# draft3_4lyr.net
KiCad netlist of a schematic drawn in EAGLE
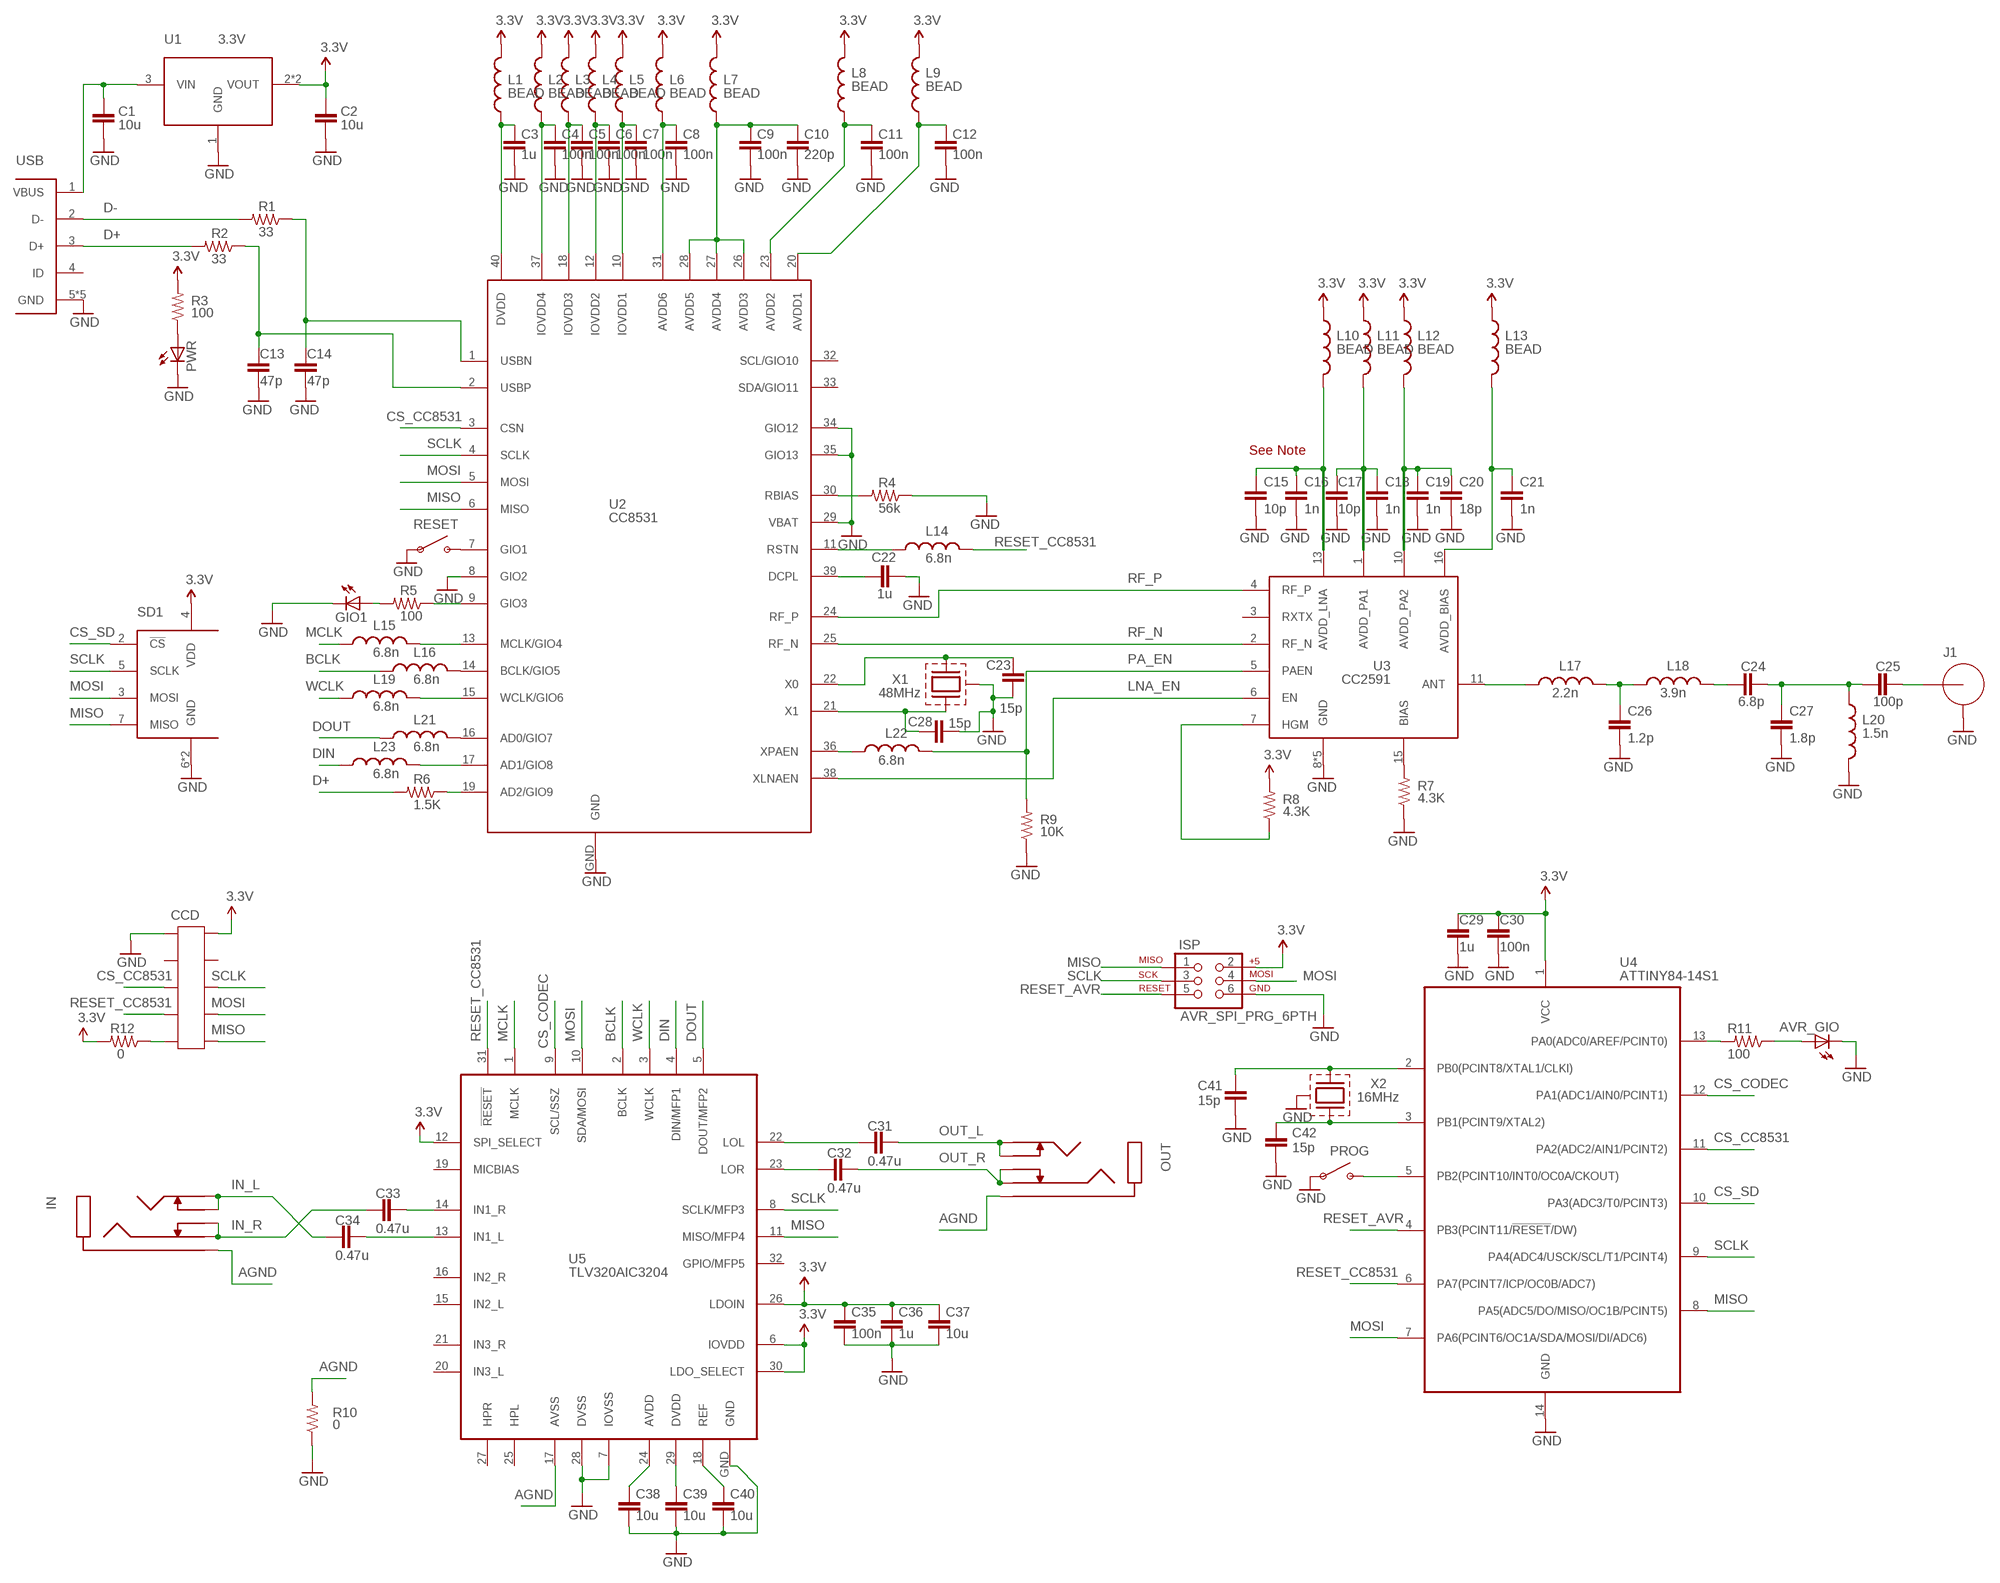
[diagram p0: schematic, sheet 1]

(export (version "E")
  (design (tool "Eeschema 10.0.6"))
  (components
    (comp (ref "AVR_GIO")
      (value "LEDCHIP-LED0603")
      (footprint "eagle-import:CHIP-LED0603")
      (libsource (lib "eagle-import") (part "LEDCHIP-LED0603"))
    )
    (comp (ref "C1")
      (value "10u")
      (footprint "eagle-import:C0603")
      (libsource (lib "eagle-import") (part "C-EUC0603"))
    )
    (comp (ref "C2")
      (value "10u")
      (footprint "eagle-import:C0603")
      (libsource (lib "eagle-import") (part "C-EUC0603"))
    )
    (comp (ref "C3")
      (value "1u")
      (footprint "eagle-import:C0603")
      (libsource (lib "eagle-import") (part "C-EUC0603"))
    )
    (comp (ref "C4")
      (value "100n")
      (footprint "eagle-import:C0603")
      (libsource (lib "eagle-import") (part "C-EUC0603"))
    )
    (comp (ref "C5")
      (value "100n")
      (footprint "eagle-import:C0603")
      (libsource (lib "eagle-import") (part "C-EUC0603"))
    )
    (comp (ref "C6")
      (value "100n")
      (footprint "eagle-import:C0603")
      (libsource (lib "eagle-import") (part "C-EUC0603"))
    )
    (comp (ref "C7")
      (value "100n")
      (footprint "eagle-import:C0603")
      (libsource (lib "eagle-import") (part "C-EUC0603"))
    )
    (comp (ref "C8")
      (value "100n")
      (footprint "eagle-import:C0603")
      (libsource (lib "eagle-import") (part "C-EUC0603"))
    )
    (comp (ref "C9")
      (value "100n")
      (footprint "eagle-import:C0603")
      (libsource (lib "eagle-import") (part "C-EUC0603"))
    )
    (comp (ref "C10")
      (value "220p")
      (footprint "eagle-import:C0603")
      (libsource (lib "eagle-import") (part "C-EUC0603"))
    )
    (comp (ref "C11")
      (value "100n")
      (footprint "eagle-import:C0603")
      (libsource (lib "eagle-import") (part "C-EUC0603"))
    )
    (comp (ref "C12")
      (value "100n")
      (footprint "eagle-import:C0603")
      (libsource (lib "eagle-import") (part "C-EUC0603"))
    )
    (comp (ref "C13")
      (value "47p")
      (footprint "eagle-import:C0603")
      (libsource (lib "eagle-import") (part "C-EUC0603"))
    )
    (comp (ref "C14")
      (value "47p")
      (footprint "eagle-import:C0603")
      (libsource (lib "eagle-import") (part "C-EUC0603"))
    )
    (comp (ref "C15")
      (value "10p")
      (footprint "eagle-import:C0603")
      (libsource (lib "eagle-import") (part "C-EUC0603"))
    )
    (comp (ref "C16")
      (value "1n")
      (footprint "eagle-import:C0603")
      (libsource (lib "eagle-import") (part "C-EUC0603"))
    )
    (comp (ref "C17")
      (value "10p")
      (footprint "eagle-import:C0603")
      (libsource (lib "eagle-import") (part "C-EUC0603"))
    )
    (comp (ref "C18")
      (value "1n")
      (footprint "eagle-import:C0603")
      (libsource (lib "eagle-import") (part "C-EUC0603"))
    )
    (comp (ref "C19")
      (value "1n")
      (footprint "eagle-import:C0603")
      (libsource (lib "eagle-import") (part "C-EUC0603"))
    )
    (comp (ref "C20")
      (value "18p")
      (footprint "eagle-import:C0603")
      (libsource (lib "eagle-import") (part "C-EUC0603"))
    )
    (comp (ref "C21")
      (value "1n")
      (footprint "eagle-import:C0603")
      (libsource (lib "eagle-import") (part "C-EUC0603"))
    )
    (comp (ref "C22")
      (value "1u")
      (footprint "eagle-import:C0603")
      (libsource (lib "eagle-import") (part "C-EUC0603"))
    )
    (comp (ref "C23")
      (value "15p")
      (footprint "eagle-import:C0603")
      (libsource (lib "eagle-import") (part "C-EUC0603"))
    )
    (comp (ref "C24")
      (value "6.8p")
      (footprint "eagle-import:C0603")
      (libsource (lib "eagle-import") (part "C-EUC0603"))
    )
    (comp (ref "C25")
      (value "100p")
      (footprint "eagle-import:C0603")
      (libsource (lib "eagle-import") (part "C-EUC0603"))
    )
    (comp (ref "C26")
      (value "1.2p")
      (footprint "eagle-import:C0603")
      (libsource (lib "eagle-import") (part "C-EUC0603"))
    )
    (comp (ref "C27")
      (value "1.8p")
      (footprint "eagle-import:C0603")
      (libsource (lib "eagle-import") (part "C-EUC0603"))
    )
    (comp (ref "C28")
      (value "15p")
      (footprint "eagle-import:C0603")
      (libsource (lib "eagle-import") (part "C-EUC0603"))
    )
    (comp (ref "C29")
      (value "1u")
      (footprint "eagle-import:C0603")
      (libsource (lib "eagle-import") (part "C-EUC0603"))
    )
    (comp (ref "C30")
      (value "100n")
      (footprint "eagle-import:C0603")
      (libsource (lib "eagle-import") (part "C-EUC0603"))
    )
    (comp (ref "C31")
      (value "0.47u")
      (footprint "eagle-import:C0603")
      (libsource (lib "eagle-import") (part "C-EUC0603"))
    )
    (comp (ref "C32")
      (value "0.47u")
      (footprint "eagle-import:C0603")
      (libsource (lib "eagle-import") (part "C-EUC0603"))
    )
    (comp (ref "C33")
      (value "0.47u")
      (footprint "eagle-import:C0603")
      (libsource (lib "eagle-import") (part "C-EUC0603"))
    )
    (comp (ref "C34")
      (value "0.47u")
      (footprint "eagle-import:C0603")
      (libsource (lib "eagle-import") (part "C-EUC0603"))
    )
    (comp (ref "C35")
      (value "100n")
      (footprint "eagle-import:C0603")
      (libsource (lib "eagle-import") (part "C-EUC0603"))
    )
    (comp (ref "C36")
      (value "1u")
      (footprint "eagle-import:C0603")
      (libsource (lib "eagle-import") (part "C-EUC0603"))
    )
    (comp (ref "C37")
      (value "10u")
      (footprint "eagle-import:C0603")
      (libsource (lib "eagle-import") (part "C-EUC0603"))
    )
    (comp (ref "C38")
      (value "10u")
      (footprint "eagle-import:C0603")
      (libsource (lib "eagle-import") (part "C-EUC0603"))
    )
    (comp (ref "C39")
      (value "10u")
      (footprint "eagle-import:C0603")
      (libsource (lib "eagle-import") (part "C-EUC0603"))
    )
    (comp (ref "C40")
      (value "10u")
      (footprint "eagle-import:C0603")
      (libsource (lib "eagle-import") (part "C-EUC0603"))
    )
    (comp (ref "C41")
      (value "15p")
      (footprint "eagle-import:C0603")
      (libsource (lib "eagle-import") (part "C-EUC0603"))
    )
    (comp (ref "C42")
      (value "15p")
      (footprint "eagle-import:C0603")
      (libsource (lib "eagle-import") (part "C-EUC0603"))
    )
    (comp (ref "CCD")
      (value "HEADER-10P-PTH-MALE")
      (footprint "eagle-import:2X5")
      (libsource (lib "eagle-import") (part "HEADER-10P-PTH-MALE"))
    )
    (comp (ref "GIO1")
      (value "LEDCHIP-LED0603")
      (footprint "eagle-import:CHIP-LED0603")
      (libsource (lib "eagle-import") (part "LEDCHIP-LED0603"))
    )
    (comp (ref "IN")
      (value "PHONE_SW")
      (footprint "eagle-import:35RAPC4BV4")
      (libsource (lib "eagle-import") (part "PHONE_SW"))
    )
    (comp (ref "ISP")
      (value "AVR_SPI_PRG_6PTH")
      (footprint "eagle-import:2X3")
      (libsource (lib "eagle-import") (part "AVR_SPI_PRG_6PTH"))
    )
    (comp (ref "J1")
      (value "SMA")
      (footprint "eagle-import:CONSMA003.031")
      (libsource (lib "eagle-import") (part "SMA"))
    )
    (comp (ref "L1")
      (value "BEAD")
      (footprint "eagle-import:0603")
      (libsource (lib "eagle-import") (part "INDUCTOR0603"))
    )
    (comp (ref "L2")
      (value "BEAD")
      (footprint "eagle-import:0603")
      (libsource (lib "eagle-import") (part "INDUCTOR0603"))
    )
    (comp (ref "L3")
      (value "BEAD")
      (footprint "eagle-import:0603")
      (libsource (lib "eagle-import") (part "INDUCTOR0603"))
    )
    (comp (ref "L4")
      (value "BEAD")
      (footprint "eagle-import:0603")
      (libsource (lib "eagle-import") (part "INDUCTOR0603"))
    )
    (comp (ref "L5")
      (value "BEAD")
      (footprint "eagle-import:0603")
      (libsource (lib "eagle-import") (part "INDUCTOR0603"))
    )
    (comp (ref "L6")
      (value "BEAD")
      (footprint "eagle-import:0603")
      (libsource (lib "eagle-import") (part "INDUCTOR0603"))
    )
    (comp (ref "L7")
      (value "BEAD")
      (footprint "eagle-import:0603")
      (libsource (lib "eagle-import") (part "INDUCTOR0603"))
    )
    (comp (ref "L8")
      (value "BEAD")
      (footprint "eagle-import:0603")
      (libsource (lib "eagle-import") (part "INDUCTOR0603"))
    )
    (comp (ref "L9")
      (value "BEAD")
      (footprint "eagle-import:0603")
      (libsource (lib "eagle-import") (part "INDUCTOR0603"))
    )
    (comp (ref "L10")
      (value "BEAD")
      (footprint "eagle-import:0603")
      (libsource (lib "eagle-import") (part "INDUCTOR0603"))
    )
    (comp (ref "L11")
      (value "BEAD")
      (footprint "eagle-import:0603")
      (libsource (lib "eagle-import") (part "INDUCTOR0603"))
    )
    (comp (ref "L12")
      (value "BEAD")
      (footprint "eagle-import:0603")
      (libsource (lib "eagle-import") (part "INDUCTOR0603"))
    )
    (comp (ref "L13")
      (value "BEAD")
      (footprint "eagle-import:0603")
      (libsource (lib "eagle-import") (part "INDUCTOR0603"))
    )
    (comp (ref "L14")
      (value "6.8n")
      (footprint "eagle-import:0603")
      (libsource (lib "eagle-import") (part "INDUCTOR0603"))
    )
    (comp (ref "L15")
      (value "6.8n")
      (footprint "eagle-import:0603")
      (libsource (lib "eagle-import") (part "INDUCTOR0603"))
    )
    (comp (ref "L16")
      (value "6.8n")
      (footprint "eagle-import:0603")
      (libsource (lib "eagle-import") (part "INDUCTOR0603"))
    )
    (comp (ref "L17")
      (value "2.2n")
      (footprint "eagle-import:0603")
      (libsource (lib "eagle-import") (part "INDUCTOR0603"))
    )
    (comp (ref "L18")
      (value "3.9n")
      (footprint "eagle-import:0603")
      (libsource (lib "eagle-import") (part "INDUCTOR0603"))
    )
    (comp (ref "L19")
      (value "6.8n")
      (footprint "eagle-import:0603")
      (libsource (lib "eagle-import") (part "INDUCTOR0603"))
    )
    (comp (ref "L20")
      (value "1.5n")
      (footprint "eagle-import:0603")
      (libsource (lib "eagle-import") (part "INDUCTOR0603"))
    )
    (comp (ref "L21")
      (value "6.8n")
      (footprint "eagle-import:0603")
      (libsource (lib "eagle-import") (part "INDUCTOR0603"))
    )
    (comp (ref "L22")
      (value "6.8n")
      (footprint "eagle-import:0603")
      (libsource (lib "eagle-import") (part "INDUCTOR0603"))
    )
    (comp (ref "L23")
      (value "6.8n")
      (footprint "eagle-import:0603")
      (libsource (lib "eagle-import") (part "INDUCTOR0603"))
    )
    (comp (ref "OUT")
      (value "PHONE_SW")
      (footprint "eagle-import:35RAPC4BV4")
      (libsource (lib "eagle-import") (part "PHONE_SW"))
    )
    (comp (ref "PROG")
      (value "SPST-SMD")
      (footprint "eagle-import:TACT_SW")
      (libsource (lib "eagle-import") (part "SPST-SMD"))
    )
    (comp (ref "PWR")
      (value "LEDCHIP-LED0603")
      (footprint "eagle-import:CHIP-LED0603")
      (libsource (lib "eagle-import") (part "LEDCHIP-LED0603"))
    )
    (comp (ref "R1")
      (value "33")
      (footprint "eagle-import:R0603")
      (libsource (lib "eagle-import") (part "R-US_R0603"))
    )
    (comp (ref "R2")
      (value "33")
      (footprint "eagle-import:R0603")
      (libsource (lib "eagle-import") (part "R-US_R0603"))
    )
    (comp (ref "R3")
      (value "100")
      (footprint "eagle-import:R0603")
      (libsource (lib "eagle-import") (part "R-US_R0603"))
    )
    (comp (ref "R4")
      (value "56k")
      (footprint "eagle-import:R0603")
      (libsource (lib "eagle-import") (part "R-US_R0603"))
    )
    (comp (ref "R5")
      (value "100")
      (footprint "eagle-import:R0603")
      (libsource (lib "eagle-import") (part "R-US_R0603"))
    )
    (comp (ref "R6")
      (value "1.5K")
      (footprint "eagle-import:R0603")
      (libsource (lib "eagle-import") (part "R-US_R0603"))
    )
    (comp (ref "R7")
      (value "4.3K")
      (footprint "eagle-import:R0603")
      (libsource (lib "eagle-import") (part "R-US_R0603"))
    )
    (comp (ref "R8")
      (value "4.3K")
      (footprint "eagle-import:R0603")
      (libsource (lib "eagle-import") (part "R-US_R0603"))
    )
    (comp (ref "R9")
      (value "10K")
      (footprint "eagle-import:R0603")
      (libsource (lib "eagle-import") (part "R-US_R0603"))
    )
    (comp (ref "R10")
      (value "0")
      (footprint "eagle-import:R0603")
      (libsource (lib "eagle-import") (part "R-US_R0603"))
    )
    (comp (ref "R11")
      (value "100")
      (footprint "eagle-import:R0603")
      (libsource (lib "eagle-import") (part "R-US_R0603"))
    )
    (comp (ref "R12")
      (value "0")
      (footprint "eagle-import:R0603")
      (libsource (lib "eagle-import") (part "R-US_R0603"))
    )
    (comp (ref "RESET")
      (value "SPST-SMD")
      (footprint "eagle-import:TACT_SW")
      (libsource (lib "eagle-import") (part "SPST-SMD"))
    )
    (comp (ref "SD1")
      (value "MICROSDDM3AT")
      (footprint "eagle-import:DM3AT")
      (libsource (lib "eagle-import") (part "MICROSDDM3AT"))
    )
    (comp (ref "U1")
      (value "3.3V")
      (footprint "eagle-import:SOT-223")
      (libsource (lib "eagle-import") (part "NX1117C"))
    )
    (comp (ref "U2")
      (value "CC8531")
      (footprint "eagle-import:S-PVQFN-N40")
      (libsource (lib "eagle-import") (part "CC8531"))
    )
    (comp (ref "U3")
      (value "CC2591")
      (footprint "eagle-import:S-PVQFN-N16")
      (libsource (lib "eagle-import") (part "CC2591"))
    )
    (comp (ref "U4")
      (value "ATTINY84-14S1")
      (footprint "eagle-import:SOIC14")
      (libsource (lib "eagle-import") (part "ATTINY84-14S1"))
    )
    (comp (ref "U5")
      (value "TLV320AIC3204")
      (footprint "eagle-import:S-PVQFN-N32")
      (libsource (lib "eagle-import") (part "TLV320AIC3204"))
    )
    (comp (ref "USB")
      (value "USB_MICRO_AB")
      (footprint "eagle-import:USB_MICRO_AB")
      (libsource (lib "eagle-import") (part "USB_MICRO_AB"))
    )
    (comp (ref "X1")
      (value "48MHz")
      (footprint "eagle-import:ABM3C")
      (libsource (lib "eagle-import") (part "XTAL-ABRACONABM3C"))
    )
    (comp (ref "X2")
      (value "16MHz")
      (footprint "eagle-import:ABMM")
      (libsource (lib "eagle-import") (part "XTAL-ABRACONABMM"))
    )
  )
  (nets
    (net (code "1") (name "/AGND") (class "Default")
      (node (ref "IN") (pin "1") (pinfunction "GND_1") (pintype "bidirectional"))
      (node (ref "OUT") (pin "1") (pinfunction "GND_1") (pintype "bidirectional"))
      (node (ref "R10") (pin "2") (pinfunction "2_2") (pintype "passive"))
      (node (ref "U5") (pin "17") (pinfunction "AVSS_17") (pintype "bidirectional"))
    )
    (net (code "2") (name "/BCLK") (class "Default")
      (node (ref "L16") (pin "1") (pinfunction "1_1") (pintype "passive"))
      (node (ref "U5") (pin "2") (pinfunction "BCLK_2") (pintype "bidirectional"))
    )
    (net (code "3") (name "/CS_CC8531") (class "Default")
      (node (ref "CCD") (pin "5") (pinfunction "5_5") (pintype "bidirectional"))
      (node (ref "U2") (pin "3") (pinfunction "CSN_3") (pintype "bidirectional"))
      (node (ref "U4") (pin "11") (pinfunction "PA2(ADC2/AIN1/PCINT2)_11") (pintype "bidirectional"))
    )
    (net (code "4") (name "/CS_CODEC") (class "Default")
      (node (ref "U4") (pin "12") (pinfunction "PA1(ADC1/AIN0/PCINT1)_12") (pintype "bidirectional"))
      (node (ref "U5") (pin "9") (pinfunction "SCL/SSZ_9") (pintype "bidirectional"))
    )
    (net (code "5") (name "/CS_SD") (class "Default")
      (node (ref "SD1") (pin "2") (pinfunction "~{CS}_2") (pintype "bidirectional"))
      (node (ref "U4") (pin "10") (pinfunction "PA3(ADC3/T0/PCINT3)_10") (pintype "bidirectional"))
    )
    (net (code "6") (name "/D+") (class "Default")
      (node (ref "R2") (pin "2") (pinfunction "2_2") (pintype "passive"))
      (node (ref "R6") (pin "2") (pinfunction "2_2") (pintype "passive"))
      (node (ref "USB") (pin "3") (pinfunction "D+_3") (pintype "bidirectional"))
    )
    (net (code "7") (name "/D-") (class "Default")
      (node (ref "R1") (pin "2") (pinfunction "2_2") (pintype "passive"))
      (node (ref "USB") (pin "2") (pinfunction "D-_2") (pintype "bidirectional"))
    )
    (net (code "8") (name "/DIN") (class "Default")
      (node (ref "L23") (pin "1") (pinfunction "1_1") (pintype "passive"))
      (node (ref "U5") (pin "4") (pinfunction "DIN/MFP1_4") (pintype "bidirectional"))
    )
    (net (code "9") (name "/DOUT") (class "Default")
      (node (ref "L21") (pin "1") (pinfunction "1_1") (pintype "passive"))
      (node (ref "U5") (pin "5") (pinfunction "DOUT/MFP2_5") (pintype "bidirectional"))
    )
    (net (code "10") (name "/IN_L") (class "Default")
      (node (ref "C34") (pin "1") (pinfunction "1_1") (pintype "passive"))
      (node (ref "IN") (pin "2") (pinfunction "L_2") (pintype "bidirectional"))
      (node (ref "IN") (pin "5") (pinfunction "L_SW_5") (pintype "bidirectional"))
    )
    (net (code "11") (name "/IN_R") (class "Default")
      (node (ref "C33") (pin "1") (pinfunction "1_1") (pintype "passive"))
      (node (ref "IN") (pin "3") (pinfunction "R_SW_3") (pintype "bidirectional"))
      (node (ref "IN") (pin "4") (pinfunction "R_4") (pintype "bidirectional"))
    )
    (net (code "12") (name "/LNA_EN") (class "Default")
      (node (ref "U2") (pin "38") (pinfunction "XLNAEN_38") (pintype "bidirectional"))
      (node (ref "U3") (pin "6") (pinfunction "EN_6") (pintype "bidirectional"))
    )
    (net (code "13") (name "/MCLK") (class "Default")
      (node (ref "L15") (pin "1") (pinfunction "1_1") (pintype "passive"))
      (node (ref "U5") (pin "1") (pinfunction "MCLK_1") (pintype "bidirectional"))
    )
    (net (code "14") (name "/MISO") (class "Default")
      (node (ref "CCD") (pin "10") (pinfunction "10_10") (pintype "bidirectional"))
      (node (ref "ISP") (pin "1") (pinfunction "1_1") (pintype "passive"))
      (node (ref "SD1") (pin "7") (pinfunction "MISO_7") (pintype "bidirectional"))
      (node (ref "U2") (pin "6") (pinfunction "MISO_6") (pintype "bidirectional"))
      (node (ref "U4") (pin "8") (pinfunction "PA5(ADC5/DO/MISO/OC1B/PCINT5)_8") (pintype "bidirectional"))
      (node (ref "U5") (pin "11") (pinfunction "MISO/MFP4_11") (pintype "bidirectional"))
    )
    (net (code "15") (name "/MOSI") (class "Default")
      (node (ref "CCD") (pin "8") (pinfunction "8_8") (pintype "bidirectional"))
      (node (ref "ISP") (pin "4") (pinfunction "4_4") (pintype "passive"))
      (node (ref "SD1") (pin "3") (pinfunction "MOSI_3") (pintype "bidirectional"))
      (node (ref "U2") (pin "5") (pinfunction "MOSI_5") (pintype "bidirectional"))
      (node (ref "U4") (pin "7") (pinfunction "PA6(PCINT6/OC1A/SDA/MOSI/DI/ADC6)_7") (pintype "bidirectional"))
      (node (ref "U5") (pin "10") (pinfunction "SDA/MOSI_10") (pintype "bidirectional"))
    )
    (net (code "16") (name "/OUT_L") (class "Default")
      (node (ref "C31") (pin "2") (pinfunction "2_2") (pintype "passive"))
      (node (ref "OUT") (pin "2") (pinfunction "L_2") (pintype "bidirectional"))
      (node (ref "OUT") (pin "5") (pinfunction "L_SW_5") (pintype "bidirectional"))
    )
    (net (code "17") (name "/OUT_R") (class "Default")
      (node (ref "C32") (pin "2") (pinfunction "2_2") (pintype "passive"))
      (node (ref "OUT") (pin "3") (pinfunction "R_SW_3") (pintype "bidirectional"))
      (node (ref "OUT") (pin "4") (pinfunction "R_4") (pintype "bidirectional"))
    )
    (net (code "18") (name "/PA_EN") (class "Default")
      (node (ref "L22") (pin "2") (pinfunction "2_2") (pintype "passive"))
      (node (ref "R9") (pin "2") (pinfunction "2_2") (pintype "passive"))
      (node (ref "U3") (pin "5") (pinfunction "PAEN_5") (pintype "bidirectional"))
    )
    (net (code "19") (name "/RESET_AVR") (class "Default")
      (node (ref "ISP") (pin "5") (pinfunction "5_5") (pintype "passive"))
      (node (ref "U4") (pin "4") (pinfunction "PB3(PCINT11/~{RESET}/DW)_4") (pintype "bidirectional"))
    )
    (net (code "20") (name "/RESET_CC8531") (class "Default")
      (node (ref "CCD") (pin "7") (pinfunction "7_7") (pintype "bidirectional"))
      (node (ref "L14") (pin "2") (pinfunction "2_2") (pintype "passive"))
      (node (ref "U4") (pin "6") (pinfunction "PA7(PCINT7/ICP/OC0B/ADC7)_6") (pintype "bidirectional"))
      (node (ref "U5") (pin "31") (pinfunction "~{RESET}_31") (pintype "bidirectional"))
    )
    (net (code "21") (name "/RF_N") (class "Default")
      (node (ref "U2") (pin "25") (pinfunction "RF_N_25") (pintype "bidirectional"))
      (node (ref "U3") (pin "2") (pinfunction "RF_N_2") (pintype "bidirectional"))
    )
    (net (code "22") (name "/RF_P") (class "Default")
      (node (ref "U2") (pin "24") (pinfunction "RF_P_24") (pintype "bidirectional"))
      (node (ref "U3") (pin "4") (pinfunction "RF_P_4") (pintype "bidirectional"))
    )
    (net (code "23") (name "/SCLK") (class "Default")
      (node (ref "CCD") (pin "6") (pinfunction "6_6") (pintype "bidirectional"))
      (node (ref "ISP") (pin "3") (pinfunction "3_3") (pintype "passive"))
      (node (ref "SD1") (pin "5") (pinfunction "SCLK_5") (pintype "bidirectional"))
      (node (ref "U2") (pin "4") (pinfunction "SCLK_4") (pintype "bidirectional"))
      (node (ref "U4") (pin "9") (pinfunction "PA4(ADC4/USCK/SCL/T1/PCINT4)_9") (pintype "bidirectional"))
      (node (ref "U5") (pin "8") (pinfunction "SCLK/MFP3_8") (pintype "bidirectional"))
    )
    (net (code "24") (name "/WCLK") (class "Default")
      (node (ref "L19") (pin "1") (pinfunction "1_1") (pintype "passive"))
      (node (ref "U5") (pin "3") (pinfunction "WCLK_3") (pintype "bidirectional"))
    )
    (net (code "25") (name "3.3V") (class "Default")
      (node (ref "C2") (pin "1") (pinfunction "1_1") (pintype "passive"))
      (node (ref "C29") (pin "1") (pinfunction "1_1") (pintype "passive"))
      (node (ref "C30") (pin "1") (pinfunction "1_1") (pintype "passive"))
      (node (ref "C35") (pin "1") (pinfunction "1_1") (pintype "passive"))
      (node (ref "C36") (pin "1") (pinfunction "1_1") (pintype "passive"))
      (node (ref "C37") (pin "1") (pinfunction "1_1") (pintype "passive"))
      (node (ref "CCD") (pin "2") (pinfunction "2_2") (pintype "bidirectional"))
      (node (ref "ISP") (pin "2") (pinfunction "2_2") (pintype "passive"))
      (node (ref "L1") (pin "2") (pinfunction "2_2") (pintype "passive"))
      (node (ref "L10") (pin "1") (pinfunction "1_1") (pintype "passive"))
      (node (ref "L11") (pin "1") (pinfunction "1_1") (pintype "passive"))
      (node (ref "L12") (pin "1") (pinfunction "1_1") (pintype "passive"))
      (node (ref "L13") (pin "1") (pinfunction "1_1") (pintype "passive"))
      (node (ref "L2") (pin "2") (pinfunction "2_2") (pintype "passive"))
      (node (ref "L3") (pin "2") (pinfunction "2_2") (pintype "passive"))
      (node (ref "L4") (pin "2") (pinfunction "2_2") (pintype "passive"))
      (node (ref "L5") (pin "2") (pinfunction "2_2") (pintype "passive"))
      (node (ref "L6") (pin "2") (pinfunction "2_2") (pintype "passive"))
      (node (ref "L7") (pin "2") (pinfunction "2_2") (pintype "passive"))
      (node (ref "L8") (pin "2") (pinfunction "2_2") (pintype "passive"))
      (node (ref "L9") (pin "2") (pinfunction "2_2") (pintype "passive"))
      (node (ref "R12") (pin "2") (pinfunction "2_2") (pintype "passive"))
      (node (ref "R3") (pin "2") (pinfunction "2_2") (pintype "passive"))
      (node (ref "R8") (pin "2") (pinfunction "2_2") (pintype "passive"))
      (node (ref "SD1") (pin "4") (pinfunction "VDD_4") (pintype "bidirectional"))
      (node (ref "U1") (pin "2") (pinfunction "VOUT_2") (pintype "bidirectional"))
      (node (ref "U1") (pin "4") (pinfunction "VOUT_4") (pintype "bidirectional"))
      (node (ref "U4") (pin "1") (pinfunction "VCC_1") (pintype "bidirectional"))
      (node (ref "U5") (pin "12") (pinfunction "SPI_SELECT_12") (pintype "bidirectional"))
      (node (ref "U5") (pin "26") (pinfunction "LDOIN_26") (pintype "bidirectional"))
      (node (ref "U5") (pin "30") (pinfunction "LDO_SELECT_30") (pintype "bidirectional"))
      (node (ref "U5") (pin "6") (pinfunction "IOVDD_6") (pintype "bidirectional"))
    )
    (net (code "26") (name "GND") (class "Default")
      (node (ref "AVR_GIO") (pin "C") (pinfunction "C_C") (pintype "passive"))
      (node (ref "C1") (pin "2") (pinfunction "2_2") (pintype "passive"))
      (node (ref "C10") (pin "2") (pinfunction "2_2") (pintype "passive"))
      (node (ref "C11") (pin "2") (pinfunction "2_2") (pintype "passive"))
      (node (ref "C12") (pin "2") (pinfunction "2_2") (pintype "passive"))
      (node (ref "C13") (pin "2") (pinfunction "2_2") (pintype "passive"))
      (node (ref "C14") (pin "2") (pinfunction "2_2") (pintype "passive"))
      (node (ref "C15") (pin "2") (pinfunction "2_2") (pintype "passive"))
      (node (ref "C16") (pin "2") (pinfunction "2_2") (pintype "passive"))
      (node (ref "C17") (pin "2") (pinfunction "2_2") (pintype "passive"))
      (node (ref "C18") (pin "2") (pinfunction "2_2") (pintype "passive"))
      (node (ref "C19") (pin "2") (pinfunction "2_2") (pintype "passive"))
      (node (ref "C2") (pin "2") (pinfunction "2_2") (pintype "passive"))
      (node (ref "C20") (pin "2") (pinfunction "2_2") (pintype "passive"))
      (node (ref "C21") (pin "2") (pinfunction "2_2") (pintype "passive"))
      (node (ref "C22") (pin "2") (pinfunction "2_2") (pintype "passive"))
      (node (ref "C23") (pin "2") (pinfunction "2_2") (pintype "passive"))
      (node (ref "C26") (pin "2") (pinfunction "2_2") (pintype "passive"))
      (node (ref "C27") (pin "2") (pinfunction "2_2") (pintype "passive"))
      (node (ref "C28") (pin "2") (pinfunction "2_2") (pintype "passive"))
      (node (ref "C29") (pin "2") (pinfunction "2_2") (pintype "passive"))
      (node (ref "C3") (pin "2") (pinfunction "2_2") (pintype "passive"))
      (node (ref "C30") (pin "2") (pinfunction "2_2") (pintype "passive"))
      (node (ref "C35") (pin "2") (pinfunction "2_2") (pintype "passive"))
      (node (ref "C36") (pin "2") (pinfunction "2_2") (pintype "passive"))
      (node (ref "C37") (pin "2") (pinfunction "2_2") (pintype "passive"))
      (node (ref "C38") (pin "2") (pinfunction "2_2") (pintype "passive"))
      (node (ref "C39") (pin "2") (pinfunction "2_2") (pintype "passive"))
      (node (ref "C4") (pin "2") (pinfunction "2_2") (pintype "passive"))
      (node (ref "C40") (pin "2") (pinfunction "2_2") (pintype "passive"))
      (node (ref "C41") (pin "1") (pinfunction "1_1") (pintype "passive"))
      (node (ref "C42") (pin "1") (pinfunction "1_1") (pintype "passive"))
      (node (ref "C5") (pin "2") (pinfunction "2_2") (pintype "passive"))
      (node (ref "C6") (pin "2") (pinfunction "2_2") (pintype "passive"))
      (node (ref "C7") (pin "2") (pinfunction "2_2") (pintype "passive"))
      (node (ref "C8") (pin "2") (pinfunction "2_2") (pintype "passive"))
      (node (ref "C9") (pin "2") (pinfunction "2_2") (pintype "passive"))
      (node (ref "CCD") (pin "1") (pinfunction "1_1") (pintype "bidirectional"))
      (node (ref "GIO1") (pin "C") (pinfunction "C_C") (pintype "passive"))
      (node (ref "ISP") (pin "6") (pinfunction "6_6") (pintype "passive"))
      (node (ref "J1") (pin "GND1") (pinfunction "GND_GND1") (pintype "bidirectional"))
      (node (ref "J1") (pin "GND2") (pinfunction "GND_GND2") (pintype "bidirectional"))
      (node (ref "J1") (pin "GND3") (pinfunction "GND_GND3") (pintype "bidirectional"))
      (node (ref "J1") (pin "GND4") (pinfunction "GND_GND4") (pintype "bidirectional"))
      (node (ref "L20") (pin "2") (pinfunction "2_2") (pintype "passive"))
      (node (ref "PROG") (pin "1") (pinfunction "P$1_1") (pintype "bidirectional"))
      (node (ref "PROG") (pin "2") (pinfunction "P$1_2") (pintype "bidirectional"))
      (node (ref "PWR") (pin "C") (pinfunction "C_C") (pintype "passive"))
      (node (ref "R10") (pin "1") (pinfunction "1_1") (pintype "passive"))
      (node (ref "R4") (pin "1") (pinfunction "1_1") (pintype "passive"))
      (node (ref "R7") (pin "1") (pinfunction "1_1") (pintype "passive"))
      (node (ref "R9") (pin "1") (pinfunction "1_1") (pintype "passive"))
      (node (ref "RESET") (pin "1") (pinfunction "P$1_1") (pintype "bidirectional"))
      (node (ref "RESET") (pin "2") (pinfunction "P$1_2") (pintype "bidirectional"))
      (node (ref "SD1") (pin "6") (pinfunction "GND_6") (pintype "bidirectional"))
      (node (ref "SD1") (pin "GND") (pinfunction "GND_GND") (pintype "bidirectional"))
      (node (ref "U1") (pin "1") (pinfunction "GND_1") (pintype "bidirectional"))
      (node (ref "U2") (pin "29") (pinfunction "VBAT_29") (pintype "bidirectional"))
      (node (ref "U2") (pin "34") (pinfunction "GIO12_34") (pintype "bidirectional"))
      (node (ref "U2") (pin "35") (pinfunction "GIO13_35") (pintype "bidirectional"))
      (node (ref "U2") (pin "8") (pinfunction "GIO2_8") (pintype "bidirectional"))
      (node (ref "U2") (pin "GND") (pinfunction "GND_GND") (pintype "bidirectional"))
      (node (ref "U3") (pin "12") (pinfunction "GND_12") (pintype "bidirectional"))
      (node (ref "U3") (pin "14") (pinfunction "GND_14") (pintype "bidirectional"))
      (node (ref "U3") (pin "8") (pinfunction "GND_8") (pintype "bidirectional"))
      (node (ref "U3") (pin "9") (pinfunction "GND_9") (pintype "bidirectional"))
      (node (ref "U3") (pin "GND") (pinfunction "GND_GND") (pintype "bidirectional"))
      (node (ref "U4") (pin "14") (pinfunction "GND_14") (pintype "bidirectional"))
      (node (ref "U5") (pin "28") (pinfunction "DVSS_28") (pintype "bidirectional"))
      (node (ref "U5") (pin "7") (pinfunction "IOVSS_7") (pintype "bidirectional"))
      (node (ref "U5") (pin "GND") (pinfunction "GND_GND") (pintype "bidirectional"))
      (node (ref "USB") (pin "5") (pinfunction "GND_5") (pintype "bidirectional"))
      (node (ref "USB") (pin "GND1") (pinfunction "GND_GND1") (pintype "bidirectional"))
      (node (ref "USB") (pin "GND2") (pinfunction "GND_GND2") (pintype "bidirectional"))
      (node (ref "USB") (pin "GND3") (pinfunction "GND_GND3") (pintype "bidirectional"))
      (node (ref "USB") (pin "GND4") (pinfunction "GND_GND4") (pintype "bidirectional"))
      (node (ref "X1") (pin "2") (pinfunction "CASE_2") (pintype "passive"))
      (node (ref "X1") (pin "4") (pinfunction "CASE_4") (pintype "passive"))
      (node (ref "X2") (pin "2") (pinfunction "CASE_2") (pintype "passive"))
      (node (ref "X2") (pin "4") (pinfunction "CASE_4") (pintype "passive"))
    )
    (net (code "27") (name "Net-(AVR_GIO-PadA)") (class "Default")
      (node (ref "AVR_GIO") (pin "A") (pinfunction "A_A") (pintype "passive"))
      (node (ref "R11") (pin "1") (pinfunction "1_1") (pintype "passive"))
    )
    (net (code "28") (name "Net-(C24-Pad1)") (class "Default")
      (node (ref "C24") (pin "1") (pinfunction "1_1") (pintype "passive"))
      (node (ref "L18") (pin "2") (pinfunction "2_2") (pintype "passive"))
    )
    (net (code "29") (name "Net-(C24-Pad2)") (class "Default")
      (node (ref "C24") (pin "2") (pinfunction "2_2") (pintype "passive"))
      (node (ref "C25") (pin "1") (pinfunction "1_1") (pintype "passive"))
      (node (ref "C27") (pin "1") (pinfunction "1_1") (pintype "passive"))
      (node (ref "L20") (pin "1") (pinfunction "1_1") (pintype "passive"))
    )
    (net (code "30") (name "Net-(C25-Pad2)") (class "Default")
      (node (ref "C25") (pin "2") (pinfunction "2_2") (pintype "passive"))
      (node (ref "J1") (pin "SIG") (pinfunction "SIG_SIG") (pintype "bidirectional"))
    )
    (net (code "31") (name "Net-(C26-Pad1)") (class "Default")
      (node (ref "C26") (pin "1") (pinfunction "1_1") (pintype "passive"))
      (node (ref "L17") (pin "2") (pinfunction "2_2") (pintype "passive"))
      (node (ref "L18") (pin "1") (pinfunction "1_1") (pintype "passive"))
    )
    (net (code "32") (name "Net-(CCD-Pad9)") (class "Default")
      (node (ref "CCD") (pin "9") (pinfunction "9_9") (pintype "bidirectional"))
      (node (ref "R12") (pin "1") (pinfunction "1_1") (pintype "passive"))
    )
    (net (code "33") (name "Net-(GIO1-PadA)") (class "Default")
      (node (ref "GIO1") (pin "A") (pinfunction "A_A") (pintype "passive"))
      (node (ref "R5") (pin "2") (pinfunction "2_2") (pintype "passive"))
    )
    (net (code "34") (name "Net-(PWR-PadA)") (class "Default")
      (node (ref "PWR") (pin "A") (pinfunction "A_A") (pintype "passive"))
      (node (ref "R3") (pin "1") (pinfunction "1_1") (pintype "passive"))
    )
    (net (code "35") (name "Net-(U1-VIN)") (class "Default")
      (node (ref "C1") (pin "1") (pinfunction "1_1") (pintype "passive"))
      (node (ref "U1") (pin "3") (pinfunction "VIN_3") (pintype "bidirectional"))
      (node (ref "USB") (pin "1") (pinfunction "VBUS_1") (pintype "bidirectional"))
    )
    (net (code "36") (name "Net-(U2-AD0{slash}GIO7)") (class "Default")
      (node (ref "L21") (pin "2") (pinfunction "2_2") (pintype "passive"))
      (node (ref "U2") (pin "16") (pinfunction "AD0/GIO7_16") (pintype "bidirectional"))
    )
    (net (code "37") (name "Net-(U2-AD1{slash}GIO8)") (class "Default")
      (node (ref "L23") (pin "2") (pinfunction "2_2") (pintype "passive"))
      (node (ref "U2") (pin "17") (pinfunction "AD1/GIO8_17") (pintype "bidirectional"))
    )
    (net (code "38") (name "Net-(U2-AD2{slash}GIO9)") (class "Default")
      (node (ref "R6") (pin "1") (pinfunction "1_1") (pintype "passive"))
      (node (ref "U2") (pin "19") (pinfunction "AD2/GIO9_19") (pintype "bidirectional"))
    )
    (net (code "39") (name "Net-(U2-AVDD1)") (class "Default")
      (node (ref "C12") (pin "1") (pinfunction "1_1") (pintype "passive"))
      (node (ref "L9") (pin "1") (pinfunction "1_1") (pintype "passive"))
      (node (ref "U2") (pin "20") (pinfunction "AVDD1_20") (pintype "bidirectional"))
    )
    (net (code "40") (name "Net-(U2-AVDD2)") (class "Default")
      (node (ref "C11") (pin "1") (pinfunction "1_1") (pintype "passive"))
      (node (ref "L8") (pin "1") (pinfunction "1_1") (pintype "passive"))
      (node (ref "U2") (pin "23") (pinfunction "AVDD2_23") (pintype "bidirectional"))
    )
    (net (code "41") (name "Net-(U2-AVDD3)") (class "Default")
      (node (ref "C10") (pin "1") (pinfunction "1_1") (pintype "passive"))
      (node (ref "C9") (pin "1") (pinfunction "1_1") (pintype "passive"))
      (node (ref "L7") (pin "1") (pinfunction "1_1") (pintype "passive"))
      (node (ref "U2") (pin "26") (pinfunction "AVDD3_26") (pintype "bidirectional"))
      (node (ref "U2") (pin "27") (pinfunction "AVDD4_27") (pintype "bidirectional"))
      (node (ref "U2") (pin "28") (pinfunction "AVDD5_28") (pintype "bidirectional"))
    )
    (net (code "42") (name "Net-(U2-AVDD6)") (class "Default")
      (node (ref "C8") (pin "1") (pinfunction "1_1") (pintype "passive"))
      (node (ref "L6") (pin "1") (pinfunction "1_1") (pintype "passive"))
      (node (ref "U2") (pin "31") (pinfunction "AVDD6_31") (pintype "bidirectional"))
    )
    (net (code "43") (name "Net-(U2-BCLK{slash}GIO5)") (class "Default")
      (node (ref "L16") (pin "2") (pinfunction "2_2") (pintype "passive"))
      (node (ref "U2") (pin "14") (pinfunction "BCLK/GIO5_14") (pintype "bidirectional"))
    )
    (net (code "44") (name "Net-(U2-DCPL)") (class "Default")
      (node (ref "C22") (pin "1") (pinfunction "1_1") (pintype "passive"))
      (node (ref "U2") (pin "39") (pinfunction "DCPL_39") (pintype "bidirectional"))
    )
    (net (code "45") (name "Net-(U2-DVDD)") (class "Default")
      (node (ref "C3") (pin "1") (pinfunction "1_1") (pintype "passive"))
      (node (ref "L1") (pin "1") (pinfunction "1_1") (pintype "passive"))
      (node (ref "U2") (pin "40") (pinfunction "DVDD_40") (pintype "bidirectional"))
    )
    (net (code "46") (name "Net-(U2-GIO1)") (class "Default")
      (node (ref "RESET") (pin "3") (pinfunction "P$2_3") (pintype "bidirectional"))
      (node (ref "RESET") (pin "4") (pinfunction "P$2_4") (pintype "bidirectional"))
      (node (ref "U2") (pin "7") (pinfunction "GIO1_7") (pintype "bidirectional"))
    )
    (net (code "47") (name "Net-(U2-GIO3)") (class "Default")
      (node (ref "R5") (pin "1") (pinfunction "1_1") (pintype "passive"))
      (node (ref "U2") (pin "9") (pinfunction "GIO3_9") (pintype "bidirectional"))
    )
    (net (code "48") (name "Net-(U2-IOVDD1)") (class "Default")
      (node (ref "C7") (pin "1") (pinfunction "1_1") (pintype "passive"))
      (node (ref "L5") (pin "1") (pinfunction "1_1") (pintype "passive"))
      (node (ref "U2") (pin "10") (pinfunction "IOVDD1_10") (pintype "bidirectional"))
    )
    (net (code "49") (name "Net-(U2-IOVDD2)") (class "Default")
      (node (ref "C6") (pin "1") (pinfunction "1_1") (pintype "passive"))
      (node (ref "L4") (pin "1") (pinfunction "1_1") (pintype "passive"))
      (node (ref "U2") (pin "12") (pinfunction "IOVDD2_12") (pintype "bidirectional"))
    )
    (net (code "50") (name "Net-(U2-IOVDD3)") (class "Default")
      (node (ref "C5") (pin "1") (pinfunction "1_1") (pintype "passive"))
      (node (ref "L3") (pin "1") (pinfunction "1_1") (pintype "passive"))
      (node (ref "U2") (pin "18") (pinfunction "IOVDD3_18") (pintype "bidirectional"))
    )
    (net (code "51") (name "Net-(U2-IOVDD4)") (class "Default")
      (node (ref "C4") (pin "1") (pinfunction "1_1") (pintype "passive"))
      (node (ref "L2") (pin "1") (pinfunction "1_1") (pintype "passive"))
      (node (ref "U2") (pin "37") (pinfunction "IOVDD4_37") (pintype "bidirectional"))
    )
    (net (code "52") (name "Net-(U2-MCLK{slash}GIO4)") (class "Default")
      (node (ref "L15") (pin "2") (pinfunction "2_2") (pintype "passive"))
      (node (ref "U2") (pin "13") (pinfunction "MCLK/GIO4_13") (pintype "bidirectional"))
    )
    (net (code "53") (name "Net-(U2-RBIAS)") (class "Default")
      (node (ref "R4") (pin "2") (pinfunction "2_2") (pintype "passive"))
      (node (ref "U2") (pin "30") (pinfunction "RBIAS_30") (pintype "bidirectional"))
    )
    (net (code "54") (name "Net-(U2-RSTN)") (class "Default")
      (node (ref "L14") (pin "1") (pinfunction "1_1") (pintype "passive"))
      (node (ref "U2") (pin "11") (pinfunction "RSTN_11") (pintype "bidirectional"))
    )
    (net (code "55") (name "Net-(U2-USBN)") (class "Default")
      (node (ref "C14") (pin "1") (pinfunction "1_1") (pintype "passive"))
      (node (ref "R1") (pin "1") (pinfunction "1_1") (pintype "passive"))
      (node (ref "U2") (pin "1") (pinfunction "USBN_1") (pintype "bidirectional"))
    )
    (net (code "56") (name "Net-(U2-USBP)") (class "Default")
      (node (ref "C13") (pin "1") (pinfunction "1_1") (pintype "passive"))
      (node (ref "R2") (pin "1") (pinfunction "1_1") (pintype "passive"))
      (node (ref "U2") (pin "2") (pinfunction "USBP_2") (pintype "bidirectional"))
    )
    (net (code "57") (name "Net-(U2-WCLK{slash}GIO6)") (class "Default")
      (node (ref "L19") (pin "2") (pinfunction "2_2") (pintype "passive"))
      (node (ref "U2") (pin "15") (pinfunction "WCLK/GIO6_15") (pintype "bidirectional"))
    )
    (net (code "58") (name "Net-(U2-X0)") (class "Default")
      (node (ref "C23") (pin "1") (pinfunction "1_1") (pintype "passive"))
      (node (ref "U2") (pin "22") (pinfunction "X0_22") (pintype "bidirectional"))
      (node (ref "X1") (pin "3") (pinfunction "2_3") (pintype "passive"))
    )
    (net (code "59") (name "Net-(U2-X1)") (class "Default")
      (node (ref "C28") (pin "1") (pinfunction "1_1") (pintype "passive"))
      (node (ref "U2") (pin "21") (pinfunction "X1_21") (pintype "bidirectional"))
      (node (ref "X1") (pin "1") (pinfunction "1_1") (pintype "passive"))
    )
    (net (code "60") (name "Net-(U2-XPAEN)") (class "Default")
      (node (ref "L22") (pin "1") (pinfunction "1_1") (pintype "passive"))
      (node (ref "U2") (pin "36") (pinfunction "XPAEN_36") (pintype "bidirectional"))
    )
    (net (code "61") (name "Net-(U3-ANT)") (class "Default")
      (node (ref "L17") (pin "1") (pinfunction "1_1") (pintype "passive"))
      (node (ref "U3") (pin "11") (pinfunction "ANT_11") (pintype "bidirectional"))
    )
    (net (code "62") (name "Net-(U3-AVDD_BIAS)") (class "Default")
      (node (ref "C21") (pin "1") (pinfunction "1_1") (pintype "passive"))
      (node (ref "L13") (pin "2") (pinfunction "2_2") (pintype "passive"))
      (node (ref "U3") (pin "16") (pinfunction "AVDD_BIAS_16") (pintype "bidirectional"))
    )
    (net (code "63") (name "Net-(U3-AVDD_LNA)") (class "Default")
      (node (ref "C15") (pin "1") (pinfunction "1_1") (pintype "passive"))
      (node (ref "C16") (pin "1") (pinfunction "1_1") (pintype "passive"))
      (node (ref "L10") (pin "2") (pinfunction "2_2") (pintype "passive"))
      (node (ref "U3") (pin "13") (pinfunction "AVDD_LNA_13") (pintype "bidirectional"))
    )
    (net (code "64") (name "Net-(U3-AVDD_PA1)") (class "Default")
      (node (ref "C17") (pin "1") (pinfunction "1_1") (pintype "passive"))
      (node (ref "C18") (pin "1") (pinfunction "1_1") (pintype "passive"))
      (node (ref "L11") (pin "2") (pinfunction "2_2") (pintype "passive"))
      (node (ref "U3") (pin "1") (pinfunction "AVDD_PA1_1") (pintype "bidirectional"))
    )
    (net (code "65") (name "Net-(U3-AVDD_PA2)") (class "Default")
      (node (ref "C19") (pin "1") (pinfunction "1_1") (pintype "passive"))
      (node (ref "C20") (pin "1") (pinfunction "1_1") (pintype "passive"))
      (node (ref "L12") (pin "2") (pinfunction "2_2") (pintype "passive"))
      (node (ref "U3") (pin "10") (pinfunction "AVDD_PA2_10") (pintype "bidirectional"))
    )
    (net (code "66") (name "Net-(U3-BIAS)") (class "Default")
      (node (ref "R7") (pin "2") (pinfunction "2_2") (pintype "passive"))
      (node (ref "U3") (pin "15") (pinfunction "BIAS_15") (pintype "bidirectional"))
    )
    (net (code "67") (name "Net-(U3-HGM)") (class "Default")
      (node (ref "R8") (pin "1") (pinfunction "1_1") (pintype "passive"))
      (node (ref "U3") (pin "7") (pinfunction "HGM_7") (pintype "bidirectional"))
    )
    (net (code "68") (name "Net-(U4-PA0(ADC0{slash}AREF{slash}PCINT0))") (class "Default")
      (node (ref "R11") (pin "2") (pinfunction "2_2") (pintype "passive"))
      (node (ref "U4") (pin "13") (pinfunction "PA0(ADC0/AREF/PCINT0)_13") (pintype "bidirectional"))
    )
    (net (code "69") (name "Net-(U4-PB0(PCINT8{slash}XTAL1{slash}CLKI))") (class "Default")
      (node (ref "C41") (pin "2") (pinfunction "2_2") (pintype "passive"))
      (node (ref "U4") (pin "2") (pinfunction "PB0(PCINT8/XTAL1/CLKI)_2") (pintype "bidirectional"))
      (node (ref "X2") (pin "1") (pinfunction "1_1") (pintype "passive"))
    )
    (net (code "70") (name "Net-(U4-PB1(PCINT9{slash}XTAL2))") (class "Default")
      (node (ref "C42") (pin "2") (pinfunction "2_2") (pintype "passive"))
      (node (ref "U4") (pin "3") (pinfunction "PB1(PCINT9/XTAL2)_3") (pintype "bidirectional"))
      (node (ref "X2") (pin "3") (pinfunction "2_3") (pintype "passive"))
    )
    (net (code "71") (name "Net-(U4-PB2(PCINT10{slash}INT0{slash}OC0A{slash}CKOUT))") (class "Default")
      (node (ref "PROG") (pin "3") (pinfunction "P$2_3") (pintype "bidirectional"))
      (node (ref "PROG") (pin "4") (pinfunction "P$2_4") (pintype "bidirectional"))
      (node (ref "U4") (pin "5") (pinfunction "PB2(PCINT10/INT0/OC0A/CKOUT)_5") (pintype "bidirectional"))
    )
    (net (code "72") (name "Net-(U5-AVDD)") (class "Default")
      (node (ref "C38") (pin "1") (pinfunction "1_1") (pintype "passive"))
      (node (ref "U5") (pin "24") (pinfunction "AVDD_24") (pintype "bidirectional"))
    )
    (net (code "73") (name "Net-(U5-DVDD)") (class "Default")
      (node (ref "C39") (pin "1") (pinfunction "1_1") (pintype "passive"))
      (node (ref "U5") (pin "29") (pinfunction "DVDD_29") (pintype "bidirectional"))
    )
    (net (code "74") (name "Net-(U5-IN1_L)") (class "Default")
      (node (ref "C34") (pin "2") (pinfunction "2_2") (pintype "passive"))
      (node (ref "U5") (pin "13") (pinfunction "IN1_L_13") (pintype "bidirectional"))
    )
    (net (code "75") (name "Net-(U5-IN1_R)") (class "Default")
      (node (ref "C33") (pin "2") (pinfunction "2_2") (pintype "passive"))
      (node (ref "U5") (pin "14") (pinfunction "IN1_R_14") (pintype "bidirectional"))
    )
    (net (code "76") (name "Net-(U5-LOL)") (class "Default")
      (node (ref "C31") (pin "1") (pinfunction "1_1") (pintype "passive"))
      (node (ref "U5") (pin "22") (pinfunction "LOL_22") (pintype "bidirectional"))
    )
    (net (code "77") (name "Net-(U5-LOR)") (class "Default")
      (node (ref "C32") (pin "1") (pinfunction "1_1") (pintype "passive"))
      (node (ref "U5") (pin "23") (pinfunction "LOR_23") (pintype "bidirectional"))
    )
    (net (code "78") (name "Net-(U5-REF)") (class "Default")
      (node (ref "C40") (pin "1") (pinfunction "1_1") (pintype "passive"))
      (node (ref "U5") (pin "18") (pinfunction "REF_18") (pintype "bidirectional"))
    )
    (net (code "79") (name "unconnected-(CCD-Pad3)") (class "Default")
      (node (ref "CCD") (pin "3") (pinfunction "3_3") (pintype "bidirectional"))
    )
    (net (code "80") (name "unconnected-(CCD-Pad4)") (class "Default")
      (node (ref "CCD") (pin "4") (pinfunction "4_4") (pintype "bidirectional"))
    )
    (net (code "81") (name "unconnected-(U2-SCL{slash}GIO10-Pad32)") (class "Default")
      (node (ref "U2") (pin "32") (pinfunction "SCL/GIO10_32") (pintype "bidirectional"))
    )
    (net (code "82") (name "unconnected-(U2-SDA{slash}GIO11-Pad33)") (class "Default")
      (node (ref "U2") (pin "33") (pinfunction "SDA/GIO11_33") (pintype "bidirectional"))
    )
    (net (code "83") (name "unconnected-(U3-RXTX-Pad3)") (class "Default")
      (node (ref "U3") (pin "3") (pinfunction "RXTX_3") (pintype "bidirectional"))
    )
    (net (code "84") (name "unconnected-(U5-GPIO{slash}MFP5-Pad32)") (class "Default")
      (node (ref "U5") (pin "32") (pinfunction "GPIO/MFP5_32") (pintype "bidirectional"))
    )
    (net (code "85") (name "unconnected-(U5-HPL-Pad25)") (class "Default")
      (node (ref "U5") (pin "25") (pinfunction "HPL_25") (pintype "bidirectional"))
    )
    (net (code "86") (name "unconnected-(U5-HPR-Pad27)") (class "Default")
      (node (ref "U5") (pin "27") (pinfunction "HPR_27") (pintype "bidirectional"))
    )
    (net (code "87") (name "unconnected-(U5-IN2_L-Pad15)") (class "Default")
      (node (ref "U5") (pin "15") (pinfunction "IN2_L_15") (pintype "bidirectional"))
    )
    (net (code "88") (name "unconnected-(U5-IN2_R-Pad16)") (class "Default")
      (node (ref "U5") (pin "16") (pinfunction "IN2_R_16") (pintype "bidirectional"))
    )
    (net (code "89") (name "unconnected-(U5-IN3_L-Pad20)") (class "Default")
      (node (ref "U5") (pin "20") (pinfunction "IN3_L_20") (pintype "bidirectional"))
    )
    (net (code "90") (name "unconnected-(U5-IN3_R-Pad21)") (class "Default")
      (node (ref "U5") (pin "21") (pinfunction "IN3_R_21") (pintype "bidirectional"))
    )
    (net (code "91") (name "unconnected-(U5-MICBIAS-Pad19)") (class "Default")
      (node (ref "U5") (pin "19") (pinfunction "MICBIAS_19") (pintype "bidirectional"))
    )
    (net (code "92") (name "unconnected-(USB-ID-Pad4)") (class "Default")
      (node (ref "USB") (pin "4") (pinfunction "ID_4") (pintype "bidirectional"))
    )
  )
)
